# Puzzle_Infrared_Temperature_Sensor_V1_0.net
KiCad netlist of a schematic drawn in EAGLE
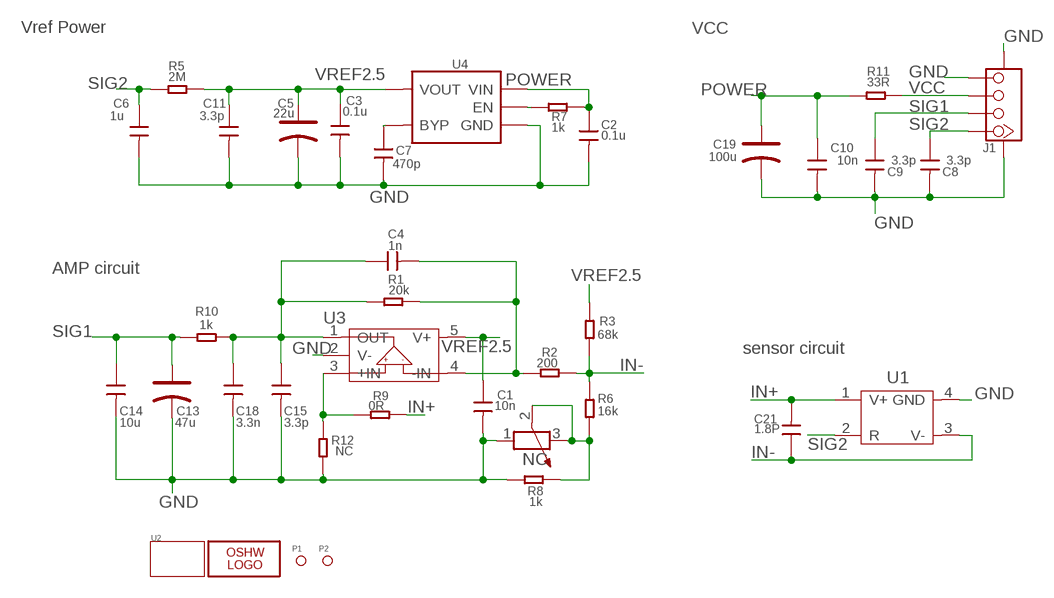
[diagram p0: schematic, sheet 1]

(export (version "E")
  (design (tool "Eeschema 10.0.6"))
  (components
    (comp (ref "C1")
      (value "10n")
      (footprint "eagle-import:0603")
      (libsource (lib "eagle-import") (part "C-0603"))
    )
    (comp (ref "C2")
      (value "0.1u")
      (footprint "eagle-import:0402")
      (libsource (lib "eagle-import") (part "C-0402"))
    )
    (comp (ref "C3")
      (value "0.1u")
      (footprint "eagle-import:0402")
      (libsource (lib "eagle-import") (part "C-0402"))
    )
    (comp (ref "C4")
      (value "1n")
      (footprint "eagle-import:0603")
      (libsource (lib "eagle-import") (part "C-0603"))
    )
    (comp (ref "C5")
      (value "22u")
      (footprint "eagle-import:AVX-A")
      (libsource (lib "eagle-import") (part "CAP-AVX-A"))
    )
    (comp (ref "C6")
      (value "1u")
      (footprint "eagle-import:0603")
      (libsource (lib "eagle-import") (part "C-0603"))
    )
    (comp (ref "C7")
      (value "470p")
      (footprint "eagle-import:0402")
      (libsource (lib "eagle-import") (part "C-0402"))
    )
    (comp (ref "C8")
      (value "3.3p")
      (footprint "eagle-import:0402")
      (libsource (lib "eagle-import") (part "C-0402"))
    )
    (comp (ref "C9")
      (value "3.3p")
      (footprint "eagle-import:0402")
      (libsource (lib "eagle-import") (part "C-0402"))
    )
    (comp (ref "C10")
      (value "10n")
      (footprint "eagle-import:0402")
      (libsource (lib "eagle-import") (part "C-0402"))
    )
    (comp (ref "C11")
      (value "3.3p")
      (footprint "eagle-import:0402")
      (libsource (lib "eagle-import") (part "C-0402"))
    )
    (comp (ref "C13")
      (value "47u")
      (footprint "eagle-import:AVX-A")
      (libsource (lib "eagle-import") (part "CAP-AVX-A"))
    )
    (comp (ref "C14")
      (value "10u")
      (footprint "eagle-import:0603")
      (libsource (lib "eagle-import") (part "C-0603"))
    )
    (comp (ref "C15")
      (value "3.3p")
      (footprint "eagle-import:0603")
      (libsource (lib "eagle-import") (part "C-0603"))
    )
    (comp (ref "C18")
      (value "3.3n")
      (footprint "eagle-import:0603")
      (libsource (lib "eagle-import") (part "C-0603"))
    )
    (comp (ref "C19")
      (value "100u")
      (footprint "eagle-import:AVX-B")
      (libsource (lib "eagle-import") (part "CAP-AVX-B"))
    )
    (comp (ref "C21")
      (value "1.8P")
      (footprint "eagle-import:0603")
      (libsource (lib "eagle-import") (part "C-0603"))
    )
    (comp (ref "J1")
      (value "TWIG-4P-2.0-SMD-FEMALE-REINFORCE'90D'")
      (footprint "eagle-import:4P-SMD-2.0-90D")
      (libsource (lib "eagle-import") (part "TWIG-4P-2.0-SMD-FEMALE-REINFORCE'90D'"))
    )
    (comp (ref "LOGO1")
      (value "LOGO-OSHW-6MILX0200-NT")
      (footprint "eagle-import:OSHW_6X200_NOTEXT")
      (libsource (lib "eagle-import") (part "LOGO-OSHW-6MILX0200-NT"))
    )
    (comp (ref "P1")
      (value "PAD-MARK")
      (footprint "eagle-import:ROUND-MARK-0.635")
      (libsource (lib "eagle-import") (part "PAD-MARK"))
    )
    (comp (ref "P2")
      (value "PAD-MARK")
      (footprint "eagle-import:ROUND-MARK-0.635")
      (libsource (lib "eagle-import") (part "PAD-MARK"))
    )
    (comp (ref "R1")
      (value "20k")
      (footprint "eagle-import:0603")
      (libsource (lib "eagle-import") (part "R-0603"))
    )
    (comp (ref "R2")
      (value "200")
      (footprint "eagle-import:0603")
      (libsource (lib "eagle-import") (part "R-0603"))
    )
    (comp (ref "R3")
      (value "68k")
      (footprint "eagle-import:0603")
      (libsource (lib "eagle-import") (part "R-0603"))
    )
    (comp (ref "R4")
      (value "NC")
      (footprint "eagle-import:3P-SMD-SQUA-3.6X3.3")
      (libsource (lib "eagle-import") (part "R-POTENTIOMETER-SMD"))
    )
    (comp (ref "R5")
      (value "2M")
      (footprint "eagle-import:0402")
      (libsource (lib "eagle-import") (part "R-0402"))
    )
    (comp (ref "R6")
      (value "16k")
      (footprint "eagle-import:0603")
      (libsource (lib "eagle-import") (part "R-0603"))
    )
    (comp (ref "R7")
      (value "1k")
      (footprint "eagle-import:0402")
      (libsource (lib "eagle-import") (part "R-0402"))
    )
    (comp (ref "R8")
      (value "1k")
      (footprint "eagle-import:0603")
      (libsource (lib "eagle-import") (part "R-0603"))
    )
    (comp (ref "R9")
      (value "0R")
      (footprint "eagle-import:0603")
      (libsource (lib "eagle-import") (part "R-0603"))
    )
    (comp (ref "R10")
      (value "1k")
      (footprint "eagle-import:0603")
      (libsource (lib "eagle-import") (part "R-0603"))
    )
    (comp (ref "R11")
      (value "33R")
      (footprint "eagle-import:0402")
      (libsource (lib "eagle-import") (part "R-0402"))
    )
    (comp (ref "R12")
      (value "NC")
      (footprint "eagle-import:0603")
      (libsource (lib "eagle-import") (part "R-0603"))
    )
    (comp (ref "U1")
      (value "SENSOR-OTP-538U")
      (footprint "eagle-import:4P-5.4MM")
      (libsource (lib "eagle-import") (part "SENSOR-OTP-538U"))
    )
    (comp (ref "U2")
      (value "TWIG-2U")
      (footprint "eagle-import:2U-DIM-W_-DRILL")
      (libsource (lib "eagle-import") (part "TWIG-2U"))
    )
    (comp (ref "U3")
      (value "OPA333")
      (footprint "eagle-import:SOT23-5")
      (libsource (lib "eagle-import") (part "OPA333"))
    )
    (comp (ref "U4")
      (value "MIC5205")
      (footprint "eagle-import:SOT23-5")
      (libsource (lib "eagle-import") (part "MIC5205"))
    )
  )
  (nets
    (net (code "1") (name "/GND") (class "Default")
      (node (ref "C1") (pin "2") (pinfunction "2_2") (pintype "passive"))
      (node (ref "C10") (pin "2") (pinfunction "2_2") (pintype "passive"))
      (node (ref "C11") (pin "2") (pinfunction "2_2") (pintype "passive"))
      (node (ref "C13") (pin "-") (pinfunction "-_-") (pintype "passive"))
      (node (ref "C14") (pin "2") (pinfunction "2_2") (pintype "passive"))
      (node (ref "C15") (pin "2") (pinfunction "2_2") (pintype "passive"))
      (node (ref "C18") (pin "2") (pinfunction "2_2") (pintype "passive"))
      (node (ref "C19") (pin "-") (pinfunction "-_-") (pintype "passive"))
      (node (ref "C2") (pin "2") (pinfunction "2_2") (pintype "passive"))
      (node (ref "C3") (pin "2") (pinfunction "2_2") (pintype "passive"))
      (node (ref "C5") (pin "-") (pinfunction "-_-") (pintype "passive"))
      (node (ref "C6") (pin "2") (pinfunction "2_2") (pintype "passive"))
      (node (ref "C7") (pin "2") (pinfunction "2_2") (pintype "passive"))
      (node (ref "C8") (pin "2") (pinfunction "2_2") (pintype "passive"))
      (node (ref "C9") (pin "2") (pinfunction "2_2") (pintype "passive"))
      (node (ref "J1") (pin "4") (pinfunction "4_4") (pintype "bidirectional"))
      (node (ref "J1") (pin "SS1") (pinfunction "SS1_SS1") (pintype "bidirectional"))
      (node (ref "J1") (pin "SS2") (pinfunction "SS2_SS2") (pintype "bidirectional"))
      (node (ref "R12") (pin "1") (pinfunction "1_1") (pintype "passive"))
      (node (ref "R4") (pin "1") (pinfunction "1_1") (pintype "passive"))
      (node (ref "R8") (pin "1") (pinfunction "1_1") (pintype "passive"))
      (node (ref "U1") (pin "4") (pinfunction "GND_4") (pintype "bidirectional"))
      (node (ref "U3") (pin "2") (pinfunction "V-_2") (pintype "bidirectional"))
      (node (ref "U4") (pin "2") (pinfunction "GND_2") (pintype "bidirectional"))
    )
    (net (code "2") (name "/IN+") (class "Default")
      (node (ref "C21") (pin "2") (pinfunction "2_2") (pintype "passive"))
      (node (ref "R9") (pin "1") (pinfunction "1_1") (pintype "passive"))
      (node (ref "U1") (pin "1") (pinfunction "V+_1") (pintype "bidirectional"))
    )
    (net (code "3") (name "/IN-") (class "Default")
      (node (ref "C21") (pin "1") (pinfunction "1_1") (pintype "passive"))
      (node (ref "R2") (pin "1") (pinfunction "1_1") (pintype "passive"))
      (node (ref "R3") (pin "2") (pinfunction "2_2") (pintype "passive"))
      (node (ref "R6") (pin "1") (pinfunction "1_1") (pintype "passive"))
      (node (ref "U1") (pin "3") (pinfunction "V-_3") (pintype "bidirectional"))
    )
    (net (code "4") (name "/POWER") (class "Default")
      (node (ref "C10") (pin "1") (pinfunction "1_1") (pintype "passive"))
      (node (ref "C19") (pin "+") (pinfunction "+_+") (pintype "passive"))
      (node (ref "C2") (pin "1") (pinfunction "1_1") (pintype "passive"))
      (node (ref "R11") (pin "1") (pinfunction "1_1") (pintype "passive"))
      (node (ref "R7") (pin "2") (pinfunction "2_2") (pintype "passive"))
      (node (ref "U4") (pin "1") (pinfunction "VIN_1") (pintype "bidirectional"))
    )
    (net (code "5") (name "/SIG1") (class "Default")
      (node (ref "C13") (pin "+") (pinfunction "+_+") (pintype "passive"))
      (node (ref "C14") (pin "1") (pinfunction "1_1") (pintype "passive"))
      (node (ref "C9") (pin "1") (pinfunction "1_1") (pintype "passive"))
      (node (ref "J1") (pin "2") (pinfunction "2_2") (pintype "bidirectional"))
      (node (ref "R10") (pin "2") (pinfunction "2_2") (pintype "passive"))
    )
    (net (code "6") (name "/SIG2") (class "Default")
      (node (ref "C6") (pin "1") (pinfunction "1_1") (pintype "passive"))
      (node (ref "C8") (pin "1") (pinfunction "1_1") (pintype "passive"))
      (node (ref "J1") (pin "1") (pinfunction "1_1") (pintype "bidirectional"))
      (node (ref "R5") (pin "1") (pinfunction "1_1") (pintype "passive"))
      (node (ref "U1") (pin "2") (pinfunction "R_2") (pintype "bidirectional"))
    )
    (net (code "7") (name "/VCC") (class "Default")
      (node (ref "J1") (pin "3") (pinfunction "3_3") (pintype "bidirectional"))
      (node (ref "R11") (pin "2") (pinfunction "2_2") (pintype "passive"))
    )
    (net (code "8") (name "/VREF2.5") (class "Default")
      (node (ref "C1") (pin "1") (pinfunction "1_1") (pintype "passive"))
      (node (ref "C11") (pin "1") (pinfunction "1_1") (pintype "passive"))
      (node (ref "C3") (pin "1") (pinfunction "1_1") (pintype "passive"))
      (node (ref "C5") (pin "+") (pinfunction "+_+") (pintype "passive"))
      (node (ref "R3") (pin "1") (pinfunction "1_1") (pintype "passive"))
      (node (ref "R5") (pin "2") (pinfunction "2_2") (pintype "passive"))
      (node (ref "U3") (pin "5") (pinfunction "V+_5") (pintype "bidirectional"))
      (node (ref "U4") (pin "5") (pinfunction "VOUT_5") (pintype "bidirectional"))
    )
    (net (code "9") (name "Net-(R4-2)") (class "Default")
      (node (ref "R4") (pin "2") (pinfunction "3_2") (pintype "passive"))
      (node (ref "R4") (pin "3") (pinfunction "2_3") (pintype "passive"))
      (node (ref "R6") (pin "2") (pinfunction "2_2") (pintype "passive"))
      (node (ref "R8") (pin "2") (pinfunction "2_2") (pintype "passive"))
    )
    (net (code "10") (name "Net-(U3-+IN)") (class "Default")
      (node (ref "R12") (pin "2") (pinfunction "2_2") (pintype "passive"))
      (node (ref "R9") (pin "2") (pinfunction "2_2") (pintype "passive"))
      (node (ref "U3") (pin "3") (pinfunction "+IN_3") (pintype "bidirectional"))
    )
    (net (code "11") (name "Net-(U3--IN)") (class "Default")
      (node (ref "C4") (pin "2") (pinfunction "2_2") (pintype "passive"))
      (node (ref "R1") (pin "1") (pinfunction "1_1") (pintype "passive"))
      (node (ref "R2") (pin "2") (pinfunction "2_2") (pintype "passive"))
      (node (ref "U3") (pin "4") (pinfunction "-IN_4") (pintype "bidirectional"))
    )
    (net (code "12") (name "Net-(U3-OUT)") (class "Default")
      (node (ref "C15") (pin "1") (pinfunction "1_1") (pintype "passive"))
      (node (ref "C18") (pin "1") (pinfunction "1_1") (pintype "passive"))
      (node (ref "C4") (pin "1") (pinfunction "1_1") (pintype "passive"))
      (node (ref "R1") (pin "2") (pinfunction "2_2") (pintype "passive"))
      (node (ref "R10") (pin "1") (pinfunction "1_1") (pintype "passive"))
      (node (ref "U3") (pin "1") (pinfunction "OUT_1") (pintype "bidirectional"))
    )
    (net (code "13") (name "Net-(U4-BYP)") (class "Default")
      (node (ref "C7") (pin "1") (pinfunction "1_1") (pintype "passive"))
      (node (ref "U4") (pin "4") (pinfunction "BYP_4") (pintype "bidirectional"))
    )
    (net (code "14") (name "Net-(U4-EN)") (class "Default")
      (node (ref "R7") (pin "1") (pinfunction "1_1") (pintype "passive"))
      (node (ref "U4") (pin "3") (pinfunction "EN_3") (pintype "bidirectional"))
    )
  )
)
